# track_charger.net
KiCad netlist of a schematic drawn in EAGLE
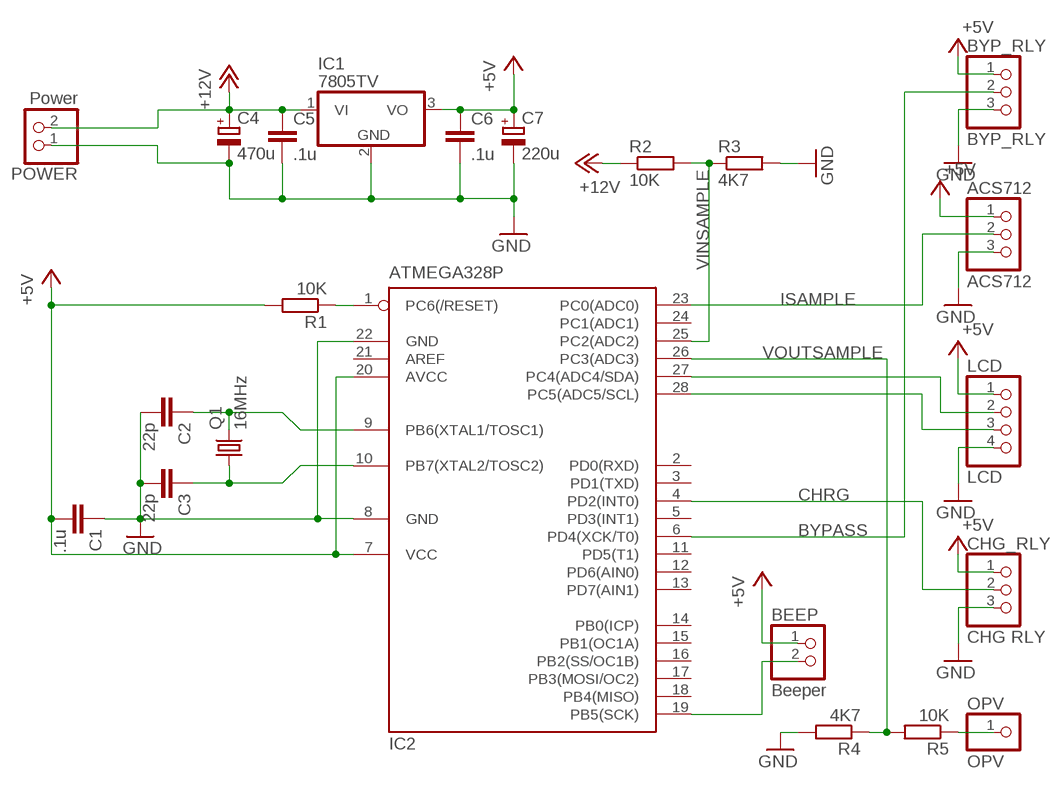
[diagram p0: schematic, sheet 1]

(export (version "E")
  (design (tool "Eeschema 10.0.6"))
  (components
    (comp (ref "ACS712")
      (value "ACS712")
      (footprint "eagle-import:1X03")
      (libsource (lib "eagle-import") (part "PINHD-1X3"))
    )
    (comp (ref "BEEP")
      (value "Beeper")
      (footprint "eagle-import:1X02")
      (libsource (lib "eagle-import") (part "PINHD-1X2"))
    )
    (comp (ref "BYP_RLY")
      (value "BYP_RLY")
      (footprint "eagle-import:1X03")
      (libsource (lib "eagle-import") (part "PINHD-1X3"))
    )
    (comp (ref "C1")
      (value ".1u")
      (footprint "eagle-import:C025-024X044")
      (libsource (lib "eagle-import") (part "C-EU025-024X044"))
    )
    (comp (ref "C2")
      (value "22p")
      (footprint "eagle-import:C025-024X044")
      (libsource (lib "eagle-import") (part "C-EU025-024X044"))
    )
    (comp (ref "C3")
      (value "22p")
      (footprint "eagle-import:C025-024X044")
      (libsource (lib "eagle-import") (part "C-EU025-024X044"))
    )
    (comp (ref "C4")
      (value "470u")
      (footprint "eagle-import:E3,5-10")
      (libsource (lib "eagle-import") (part "CPOL-EUE3.5-10"))
    )
    (comp (ref "C5")
      (value ".1u")
      (footprint "eagle-import:C025-024X044")
      (libsource (lib "eagle-import") (part "C-EU025-024X044"))
    )
    (comp (ref "C6")
      (value ".1u")
      (footprint "eagle-import:C025-024X044")
      (libsource (lib "eagle-import") (part "C-EU025-024X044"))
    )
    (comp (ref "C7")
      (value "220u")
      (footprint "eagle-import:E2,5-7")
      (libsource (lib "eagle-import") (part "CPOL-EUE2.5-7"))
    )
    (comp (ref "CHG_RLY")
      (value "CHG RLY")
      (footprint "eagle-import:1X03")
      (libsource (lib "eagle-import") (part "PINHD-1X3"))
    )
    (comp (ref "IC1")
      (value "7805TV")
      (footprint "eagle-import:TO220V")
      (libsource (lib "eagle-import") (part "78TV05"))
    )
    (comp (ref "IC2")
      (value "ATMEGA328P")
      (footprint "eagle-import:DIL28-3")
      (libsource (lib "eagle-import") (part "MEGA8-P"))
    )
    (comp (ref "LCD")
      (value "LCD")
      (footprint "eagle-import:1X04")
      (libsource (lib "eagle-import") (part "PINHD-1X4"))
    )
    (comp (ref "OPV")
      (value "OPV")
      (footprint "eagle-import:1X01")
      (libsource (lib "eagle-import") (part "PINHD-1X1"))
    )
    (comp (ref "POWER")
      (value "Power")
      (footprint "eagle-import:1X02")
      (libsource (lib "eagle-import") (part "PINHD-1X2"))
    )
    (comp (ref "Q1")
      (value "16MHz")
      (footprint "eagle-import:HC18U-V")
      (libsource (lib "eagle-import") (part "CRYSTALHC18U-V"))
    )
    (comp (ref "R1")
      (value "10K")
      (footprint "eagle-import:0204_7")
      (libsource (lib "eagle-import") (part "R-EU_0204/7"))
    )
    (comp (ref "R2")
      (value "10K")
      (footprint "eagle-import:0204_7")
      (libsource (lib "eagle-import") (part "R-EU_0204/7"))
    )
    (comp (ref "R3")
      (value "4K7")
      (footprint "eagle-import:0204_7")
      (libsource (lib "eagle-import") (part "R-EU_0204/7"))
    )
    (comp (ref "R4")
      (value "4K7")
      (footprint "eagle-import:0204_7")
      (libsource (lib "eagle-import") (part "R-EU_0204/7"))
    )
    (comp (ref "R5")
      (value "10K")
      (footprint "eagle-import:0204_7")
      (libsource (lib "eagle-import") (part "R-EU_0204/7"))
    )
  )
  (nets
    (net (code "1") (name "+5V") (class "Default")
      (node (ref "ACS712") (pin "1") (pinfunction "1_1") (pintype "passive"))
      (node (ref "BEEP") (pin "1") (pinfunction "1_1") (pintype "passive"))
      (node (ref "BYP_RLY") (pin "1") (pinfunction "1_1") (pintype "passive"))
      (node (ref "C1") (pin "2") (pinfunction "2_2") (pintype "passive"))
      (node (ref "C6") (pin "1") (pinfunction "1_1") (pintype "passive"))
      (node (ref "C7") (pin "+") (pinfunction "+_+") (pintype "passive"))
      (node (ref "CHG_RLY") (pin "1") (pinfunction "1_1") (pintype "passive"))
      (node (ref "IC1") (pin "3") (pinfunction "VO_3") (pintype "passive"))
      (node (ref "IC2") (pin "20") (pinfunction "AVCC_20") (pintype "power_in"))
      (node (ref "IC2") (pin "7") (pinfunction "VCC_7") (pintype "power_in"))
      (node (ref "LCD") (pin "1") (pinfunction "1_1") (pintype "passive"))
      (node (ref "R1") (pin "2") (pinfunction "2_2") (pintype "passive"))
    )
    (net (code "2") (name "+12V") (class "Default")
      (node (ref "C4") (pin "+") (pinfunction "+_+") (pintype "passive"))
      (node (ref "C5") (pin "1") (pinfunction "1_1") (pintype "passive"))
      (node (ref "IC1") (pin "1") (pinfunction "VI_1") (pintype "input"))
      (node (ref "POWER") (pin "2") (pinfunction "2_2") (pintype "passive"))
      (node (ref "R2") (pin "1") (pinfunction "1_1") (pintype "passive"))
    )
    (net (code "3") (name "/BYPASS") (class "Default")
      (node (ref "BYP_RLY") (pin "2") (pinfunction "2_2") (pintype "passive"))
      (node (ref "IC2") (pin "6") (pinfunction "PD4(XCK/T0)_6") (pintype "bidirectional"))
    )
    (net (code "4") (name "/CHRG") (class "Default")
      (node (ref "CHG_RLY") (pin "2") (pinfunction "2_2") (pintype "passive"))
      (node (ref "IC2") (pin "4") (pinfunction "PD2(INT0)_4") (pintype "bidirectional"))
    )
    (net (code "5") (name "/ISAMPLE") (class "Default")
      (node (ref "ACS712") (pin "2") (pinfunction "2_2") (pintype "passive"))
      (node (ref "IC2") (pin "23") (pinfunction "PC0(ADC0)_23") (pintype "bidirectional"))
    )
    (net (code "6") (name "/VINSAMPLE") (class "Default")
      (node (ref "IC2") (pin "25") (pinfunction "PC2(ADC2)_25") (pintype "bidirectional"))
      (node (ref "R2") (pin "2") (pinfunction "2_2") (pintype "passive"))
      (node (ref "R3") (pin "1") (pinfunction "1_1") (pintype "passive"))
    )
    (net (code "7") (name "/VOUTSAMPLE") (class "Default")
      (node (ref "IC2") (pin "26") (pinfunction "PC3(ADC3)_26") (pintype "bidirectional"))
      (node (ref "R4") (pin "1") (pinfunction "1_1") (pintype "passive"))
      (node (ref "R5") (pin "2") (pinfunction "2_2") (pintype "passive"))
    )
    (net (code "8") (name "GND") (class "Default")
      (node (ref "ACS712") (pin "3") (pinfunction "3_3") (pintype "passive"))
      (node (ref "BYP_RLY") (pin "3") (pinfunction "3_3") (pintype "passive"))
      (node (ref "C1") (pin "1") (pinfunction "1_1") (pintype "passive"))
      (node (ref "C2") (pin "2") (pinfunction "2_2") (pintype "passive"))
      (node (ref "C3") (pin "2") (pinfunction "2_2") (pintype "passive"))
      (node (ref "C4") (pin "-") (pinfunction "-_-") (pintype "passive"))
      (node (ref "C5") (pin "2") (pinfunction "2_2") (pintype "passive"))
      (node (ref "C6") (pin "2") (pinfunction "2_2") (pintype "passive"))
      (node (ref "C7") (pin "-") (pinfunction "-_-") (pintype "passive"))
      (node (ref "CHG_RLY") (pin "3") (pinfunction "3_3") (pintype "passive"))
      (node (ref "IC1") (pin "2") (pinfunction "GND_2") (pintype "passive"))
      (node (ref "IC2") (pin "22") (pinfunction "GND_22") (pintype "power_in"))
      (node (ref "IC2") (pin "8") (pinfunction "GND_8") (pintype "power_in"))
      (node (ref "LCD") (pin "4") (pinfunction "4_4") (pintype "passive"))
      (node (ref "POWER") (pin "1") (pinfunction "1_1") (pintype "passive"))
      (node (ref "R3") (pin "2") (pinfunction "2_2") (pintype "passive"))
      (node (ref "R4") (pin "2") (pinfunction "2_2") (pintype "passive"))
    )
    (net (code "9") (name "Net-(IC2-PB5(SCK))") (class "Default")
      (node (ref "BEEP") (pin "2") (pinfunction "2_2") (pintype "passive"))
      (node (ref "IC2") (pin "19") (pinfunction "PB5(SCK)_19") (pintype "bidirectional"))
    )
    (net (code "10") (name "Net-(IC2-PB6(XTAL1{slash}TOSC1))") (class "Default")
      (node (ref "C2") (pin "1") (pinfunction "1_1") (pintype "passive"))
      (node (ref "IC2") (pin "9") (pinfunction "PB6(XTAL1/TOSC1)_9") (pintype "bidirectional"))
      (node (ref "Q1") (pin "2") (pinfunction "2_2") (pintype "passive"))
    )
    (net (code "11") (name "Net-(IC2-PB7(XTAL2{slash}TOSC2))") (class "Default")
      (node (ref "C3") (pin "1") (pinfunction "1_1") (pintype "passive"))
      (node (ref "IC2") (pin "10") (pinfunction "PB7(XTAL2/TOSC2)_10") (pintype "bidirectional"))
      (node (ref "Q1") (pin "1") (pinfunction "1_1") (pintype "passive"))
    )
    (net (code "12") (name "Net-(IC2-PC4(ADC4{slash}SDA))") (class "Default")
      (node (ref "IC2") (pin "27") (pinfunction "PC4(ADC4/SDA)_27") (pintype "bidirectional"))
      (node (ref "LCD") (pin "2") (pinfunction "2_2") (pintype "passive"))
    )
    (net (code "13") (name "Net-(IC2-PC5(ADC5{slash}SCL))") (class "Default")
      (node (ref "IC2") (pin "28") (pinfunction "PC5(ADC5/SCL)_28") (pintype "bidirectional"))
      (node (ref "LCD") (pin "3") (pinfunction "3_3") (pintype "passive"))
    )
    (net (code "14") (name "Net-(IC2-PC6({slash}RESET))") (class "Default")
      (node (ref "IC2") (pin "1") (pinfunction "PC6(/RESET)_1") (pintype "bidirectional"))
      (node (ref "R1") (pin "1") (pinfunction "1_1") (pintype "passive"))
    )
    (net (code "15") (name "Net-(OPV-Pad1)") (class "Default")
      (node (ref "OPV") (pin "1") (pinfunction "1_1") (pintype "passive"))
      (node (ref "R5") (pin "1") (pinfunction "1_1") (pintype "passive"))
    )
    (net (code "16") (name "unconnected-(IC2-AREF-Pad21)") (class "Default")
      (node (ref "IC2") (pin "21") (pinfunction "AREF_21") (pintype "passive"))
    )
    (net (code "17") (name "unconnected-(IC2-PB0(ICP)-Pad14)") (class "Default")
      (node (ref "IC2") (pin "14") (pinfunction "PB0(ICP)_14") (pintype "bidirectional"))
    )
    (net (code "18") (name "unconnected-(IC2-PB1(OC1A)-Pad15)") (class "Default")
      (node (ref "IC2") (pin "15") (pinfunction "PB1(OC1A)_15") (pintype "bidirectional"))
    )
    (net (code "19") (name "unconnected-(IC2-PB2(SS{slash}OC1B)-Pad16)") (class "Default")
      (node (ref "IC2") (pin "16") (pinfunction "PB2(SS/OC1B)_16") (pintype "bidirectional"))
    )
    (net (code "20") (name "unconnected-(IC2-PB3(MOSI{slash}OC2)-Pad17)") (class "Default")
      (node (ref "IC2") (pin "17") (pinfunction "PB3(MOSI/OC2)_17") (pintype "bidirectional"))
    )
    (net (code "21") (name "unconnected-(IC2-PB4(MISO)-Pad18)") (class "Default")
      (node (ref "IC2") (pin "18") (pinfunction "PB4(MISO)_18") (pintype "bidirectional"))
    )
    (net (code "22") (name "unconnected-(IC2-PC1(ADC1)-Pad24)") (class "Default")
      (node (ref "IC2") (pin "24") (pinfunction "PC1(ADC1)_24") (pintype "bidirectional"))
    )
    (net (code "23") (name "unconnected-(IC2-PD0(RXD)-Pad2)") (class "Default")
      (node (ref "IC2") (pin "2") (pinfunction "PD0(RXD)_2") (pintype "bidirectional"))
    )
    (net (code "24") (name "unconnected-(IC2-PD1(TXD)-Pad3)") (class "Default")
      (node (ref "IC2") (pin "3") (pinfunction "PD1(TXD)_3") (pintype "bidirectional"))
    )
    (net (code "25") (name "unconnected-(IC2-PD3(INT1)-Pad5)") (class "Default")
      (node (ref "IC2") (pin "5") (pinfunction "PD3(INT1)_5") (pintype "bidirectional"))
    )
    (net (code "26") (name "unconnected-(IC2-PD5(T1)-Pad11)") (class "Default")
      (node (ref "IC2") (pin "11") (pinfunction "PD5(T1)_11") (pintype "bidirectional"))
    )
    (net (code "27") (name "unconnected-(IC2-PD6(AIN0)-Pad12)") (class "Default")
      (node (ref "IC2") (pin "12") (pinfunction "PD6(AIN0)_12") (pintype "bidirectional"))
    )
    (net (code "28") (name "unconnected-(IC2-PD7(AIN1)-Pad13)") (class "Default")
      (node (ref "IC2") (pin "13") (pinfunction "PD7(AIN1)_13") (pintype "bidirectional"))
    )
  )
)
